# Battery_manager.net
KiCad netlist of a schematic drawn in Altium Designer
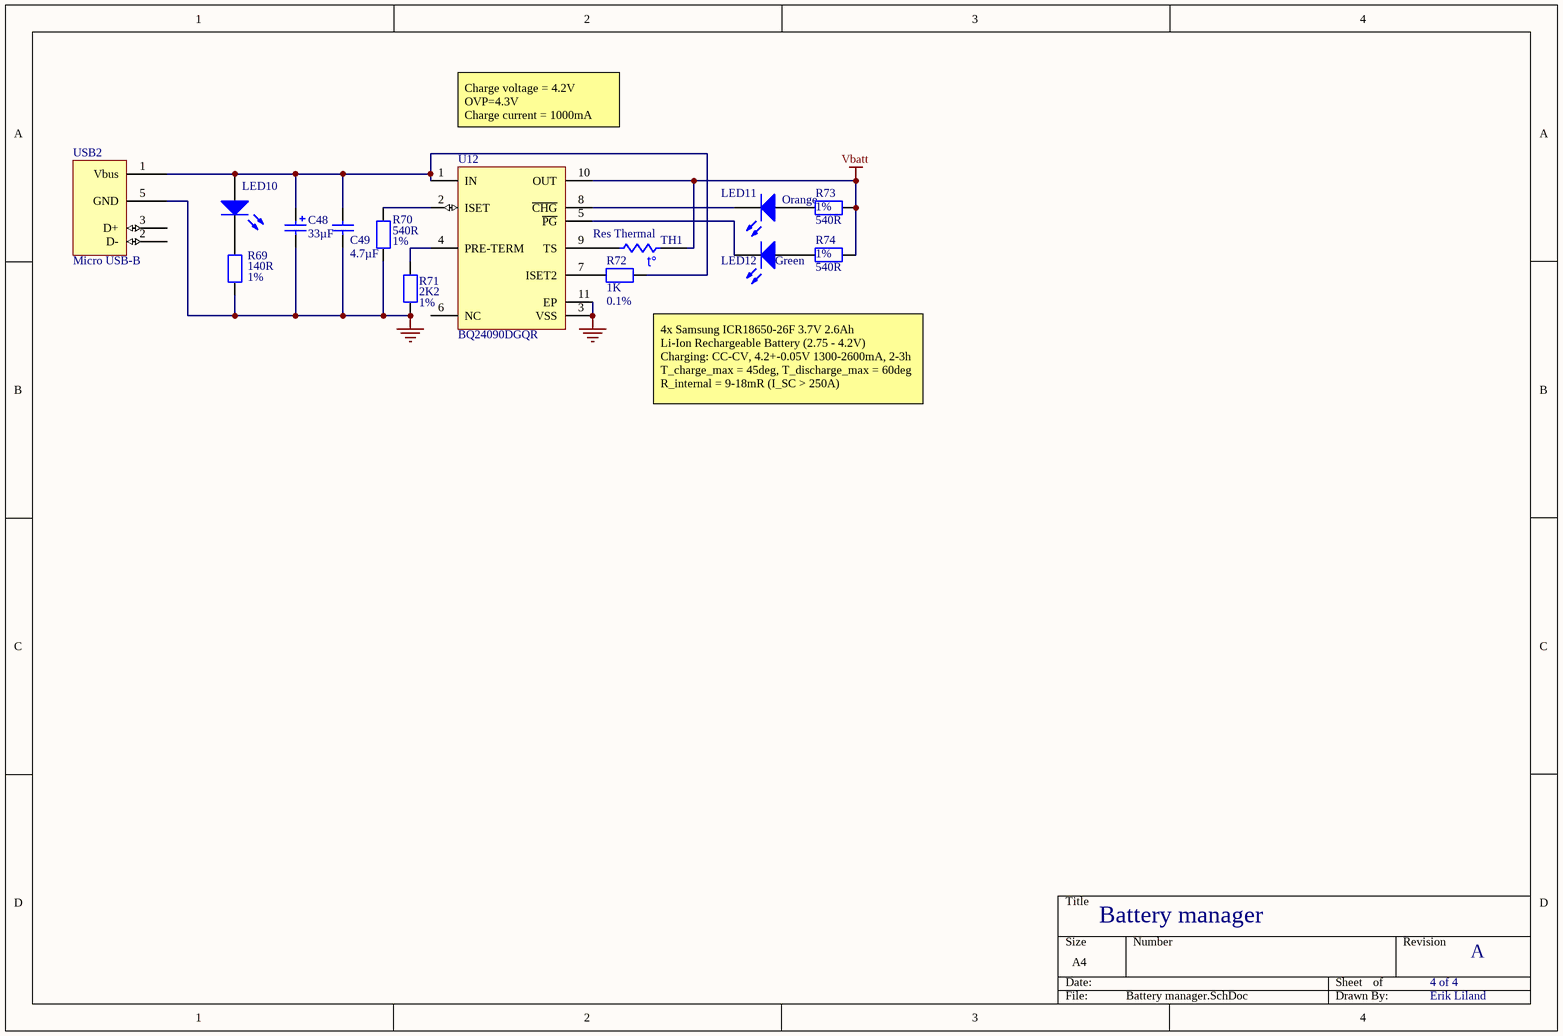
[diagram p0: Battery manager.SchDoc]

(export (version "E")
  (design (tool "Eeschema 10.0.6"))
  (components
    (comp (ref "C48")
      (value "33µF")
      (footprint "BatteruPSU:CAP SMD (F)")
      (description "Polarized Capacitor")
      (fields
        (field (name "MANUFACTURER") "Panasonic Electronic Components")
        (field (name "MANUFACTURER PART NUMBER") "EEH-ZA1E330R")
      )
      (libsource (lib "BatteryPSU-parts") (part "Cap Pol"))
    )
    (comp (ref "C49")
      (value "4.7µF")
      (footprint "BatteruPSU:0805_N_CAP")
      (description "Capacitor")
      (fields
        (field (name "MANUFACTURER") "Samsung Electro-Mechanics America, Inc")
        (field (name "MANUFACTURER PART NUMBER") "CL21B475KOFNFNE")
      )
      (libsource (lib "BatteryPSU-parts") (part "Cap"))
    )
    (comp (ref "LED10")
      (value "LED")
      (footprint "BatteruPSU:0805_N_LED")
      (description "Typical RED, GREEN, YELLOW, AMBER")
      (fields
        (field (name "MANUFACTURER") "OSRAM Opto Semiconductors Inc")
        (field (name "MANUFACTURER PART NUMBER") "LG R971-KN-1")
      )
      (libsource (lib "BatteryPSU-parts") (part "LED"))
    )
    (comp (ref "LED11")
      (value "Orange")
      (footprint "BatteruPSU:LED ANGLE SMD YELLOW")
      (description "Horisontal LED")
      (fields
        (field (name "MANUFACTURER") "Kingbright")
        (field (name "MANUFACTURER PART NUMBER") "APA3010SECK-GX")
      )
      (libsource (lib "BatteryPSU-parts") (part "LED HOR"))
    )
    (comp (ref "LED12")
      (value "Green")
      (footprint "BatteruPSU:LED ANGLE SMD GREEN")
      (description "Horisontal LED")
      (fields
        (field (name "MANUFACTURER") "Kingbright")
        (field (name "MANUFACTURER PART NUMBER") "APA3010SECK-GX")
      )
      (libsource (lib "BatteryPSU-parts") (part "LED HOR"))
    )
    (comp (ref "R69")
      (value "140R")
      (footprint "BatteruPSU:0805_N_RES")
      (description "Resistor")
      (fields
        (field (name "TOLERANCE") "1%")
        (field (name "MANUFACTURER") "Samsung Electro-Mechanics America, Inc")
        (field (name "MANUFACTURER PART NUMBER") "RC2012F1400CS")
      )
      (libsource (lib "") (part "Res_1"))
    )
    (comp (ref "R70")
      (value "540R")
      (footprint "BatteruPSU:0805_N_RES")
      (description "Resistor")
      (fields (field (name "TOLERANCE") "1%"))
      (libsource (lib "") (part "Res_1"))
    )
    (comp (ref "R71")
      (value "2K2")
      (footprint "BatteruPSU:0805_N_RES")
      (description "Resistor")
      (fields
        (field (name "TOLERANCE") "1%")
        (field (name "MANUFACTURER") "Samsung Electro-Mechanics America, Inc")
        (field (name "MANUFACTURER PART NUMBER") "RC2012F222CS")
      )
      (libsource (lib "") (part "Res_1"))
    )
    (comp (ref "R72")
      (value "1K")
      (footprint "BatteruPSU:0805_N_RES")
      (description "Resistor")
      (fields
        (field (name "TOLERANCE") "0.1%")
        (field (name "MANUFACTURER") "Panasonic Electronic Components")
        (field (name "MANUFACTURER PART NUMBER") "ERA-6AEB102V")
      )
      (libsource (lib "BatteryPSU-parts") (part "Res"))
    )
    (comp (ref "R73")
      (value "540R")
      (footprint "BatteruPSU:0805_N_RES")
      (description "Resistor")
      (fields (field (name "TOLERANCE") "1%"))
      (libsource (lib "BatteryPSU-parts") (part "Res"))
    )
    (comp (ref "R74")
      (value "540R")
      (footprint "BatteruPSU:0805_N_RES")
      (description "Resistor")
      (fields (field (name "TOLERANCE") "1%"))
      (libsource (lib "BatteryPSU-parts") (part "Res"))
    )
    (comp (ref "TH1")
      (value "Res Thermal")
      (footprint "BatteruPSU:HDR1X2")
      (description "Thermistor")
      (fields
        (field (name "MANUFACTURER") "Harwin Inc")
        (field (name "MANUFACTURER PART NUMBER") "M20-9990246")
        (field (name "PUBLISHER") "Altium Limited")
      )
      (libsource (lib "BatteryPSU-parts") (part "Res Thermal"))
    )
    (comp (ref "U12")
      (value "BQ24090DGQR")
      (footprint "DGQ10-1675X1445TP_M")
      (fields (field (name "MANUFACTURER") "Texas Instruments"))
      (libsource (lib "Altium Content Vault") (part "CMP-0321-00917-1"))
    )
    (comp (ref "USB2")
      (value "Micro USB-B")
      (footprint "BatteruPSU:USB_TYPEB_SMD")
      (description "Horisontal micro usb b")
      (fields (field (name "MANUFACTURER") "FCI") (field (name "MANUFACTURER PART NUMBER") "10118194-0001LF"))
      (libsource (lib "BatteryPSU-parts") (part "USB_micro_B"))
    )
  )
  (nets
    (net (code "1") (name "GND") (class "Default")
      (node (ref "C48") (pin "2") (pinfunction "2_2") (pintype "passive"))
      (node (ref "C49") (pin "2") (pinfunction "2_2") (pintype "passive"))
      (node (ref "R69") (pin "1") (pinfunction "1_1") (pintype "passive"))
      (node (ref "R70") (pin "1") (pinfunction "1_1") (pintype "passive"))
      (node (ref "R71") (pin "1") (pinfunction "1_1") (pintype "passive"))
      (node (ref "U12") (pin "11") (pinfunction "EP_11") (pintype "power_in"))
      (node (ref "U12") (pin "3") (pinfunction "VSS_3") (pintype "power_in"))
      (node (ref "USB2") (pin "5") (pinfunction "GND_5") (pintype "passive"))
    )
    (net (code "2") (name "Net-(LED10-A)") (class "Default")
      (node (ref "C48") (pin "1") (pinfunction "1_1") (pintype "passive"))
      (node (ref "C49") (pin "1") (pinfunction "1_1") (pintype "passive"))
      (node (ref "LED10") (pin "1") (pinfunction "A_1") (pintype "passive"))
      (node (ref "R72") (pin "1") (pinfunction "1_1") (pintype "passive"))
      (node (ref "U12") (pin "1") (pinfunction "IN_1") (pintype "power_in"))
      (node (ref "USB2") (pin "1") (pinfunction "Vbus_1") (pintype "power_in"))
    )
    (net (code "3") (name "Net-(LED10-K)") (class "Default")
      (node (ref "LED10") (pin "2") (pinfunction "K_2") (pintype "passive"))
      (node (ref "R69") (pin "2") (pinfunction "2_2") (pintype "passive"))
    )
    (net (code "4") (name "Net-(LED11-A)") (class "Default")
      (node (ref "LED11") (pin "1") (pinfunction "A_1") (pintype "passive"))
      (node (ref "R73") (pin "2") (pinfunction "2_2") (pintype "passive"))
    )
    (net (code "5") (name "Net-(LED11-K)") (class "Default")
      (node (ref "LED11") (pin "2") (pinfunction "K_2") (pintype "passive"))
      (node (ref "U12") (pin "8") (pinfunction "~{CHG}_8") (pintype "tri_state"))
    )
    (net (code "6") (name "Net-(LED12-A)") (class "Default")
      (node (ref "LED12") (pin "1") (pinfunction "A_1") (pintype "passive"))
      (node (ref "R74") (pin "2") (pinfunction "2_2") (pintype "passive"))
    )
    (net (code "7") (name "Net-(LED12-K)") (class "Default")
      (node (ref "LED12") (pin "2") (pinfunction "K_2") (pintype "passive"))
      (node (ref "U12") (pin "5") (pinfunction "~{PG}_5") (pintype "tri_state"))
    )
    (net (code "8") (name "Net-(U12-ISET)") (class "Default")
      (node (ref "R70") (pin "2") (pinfunction "2_2") (pintype "passive"))
      (node (ref "U12") (pin "2") (pinfunction "ISET_2") (pintype "bidirectional"))
    )
    (net (code "9") (name "Net-(U12-ISET2)") (class "Default")
      (node (ref "R72") (pin "2") (pinfunction "2_2") (pintype "passive"))
      (node (ref "U12") (pin "7") (pinfunction "ISET2_7") (pintype "passive"))
    )
    (net (code "10") (name "Net-(U12-PRE-TERM)") (class "Default")
      (node (ref "R71") (pin "2") (pinfunction "2_2") (pintype "passive"))
      (node (ref "U12") (pin "4") (pinfunction "PRE-TERM_4") (pintype "passive"))
    )
    (net (code "11") (name "Net-(U12-TS)") (class "Default")
      (node (ref "TH1") (pin "2") (pinfunction "2_2") (pintype "passive"))
      (node (ref "U12") (pin "9") (pinfunction "TS_9") (pintype "passive"))
    )
    (net (code "12") (name "Vbatt") (class "Default")
      (node (ref "R73") (pin "1") (pinfunction "1_1") (pintype "passive"))
      (node (ref "R74") (pin "1") (pinfunction "1_1") (pintype "passive"))
      (node (ref "TH1") (pin "1") (pinfunction "1_1") (pintype "passive"))
      (node (ref "U12") (pin "10") (pinfunction "OUT_10") (pintype "power_in"))
    )
    (net (code "13") (name "unconnected-(U12-NC-Pad6)") (class "Default")
      (node (ref "U12") (pin "6") (pinfunction "NC_6") (pintype "passive"))
    )
    (net (code "14") (name "unconnected-(USB2-D+-Pad3)") (class "Default")
      (node (ref "USB2") (pin "3") (pinfunction "D+_3") (pintype "bidirectional"))
    )
    (net (code "15") (name "unconnected-(USB2-D--Pad2)") (class "Default")
      (node (ref "USB2") (pin "2") (pinfunction "D-_2") (pintype "bidirectional"))
    )
  )
)
